# Schematic.net
KiCad netlist of a schematic drawn in Altium Designer
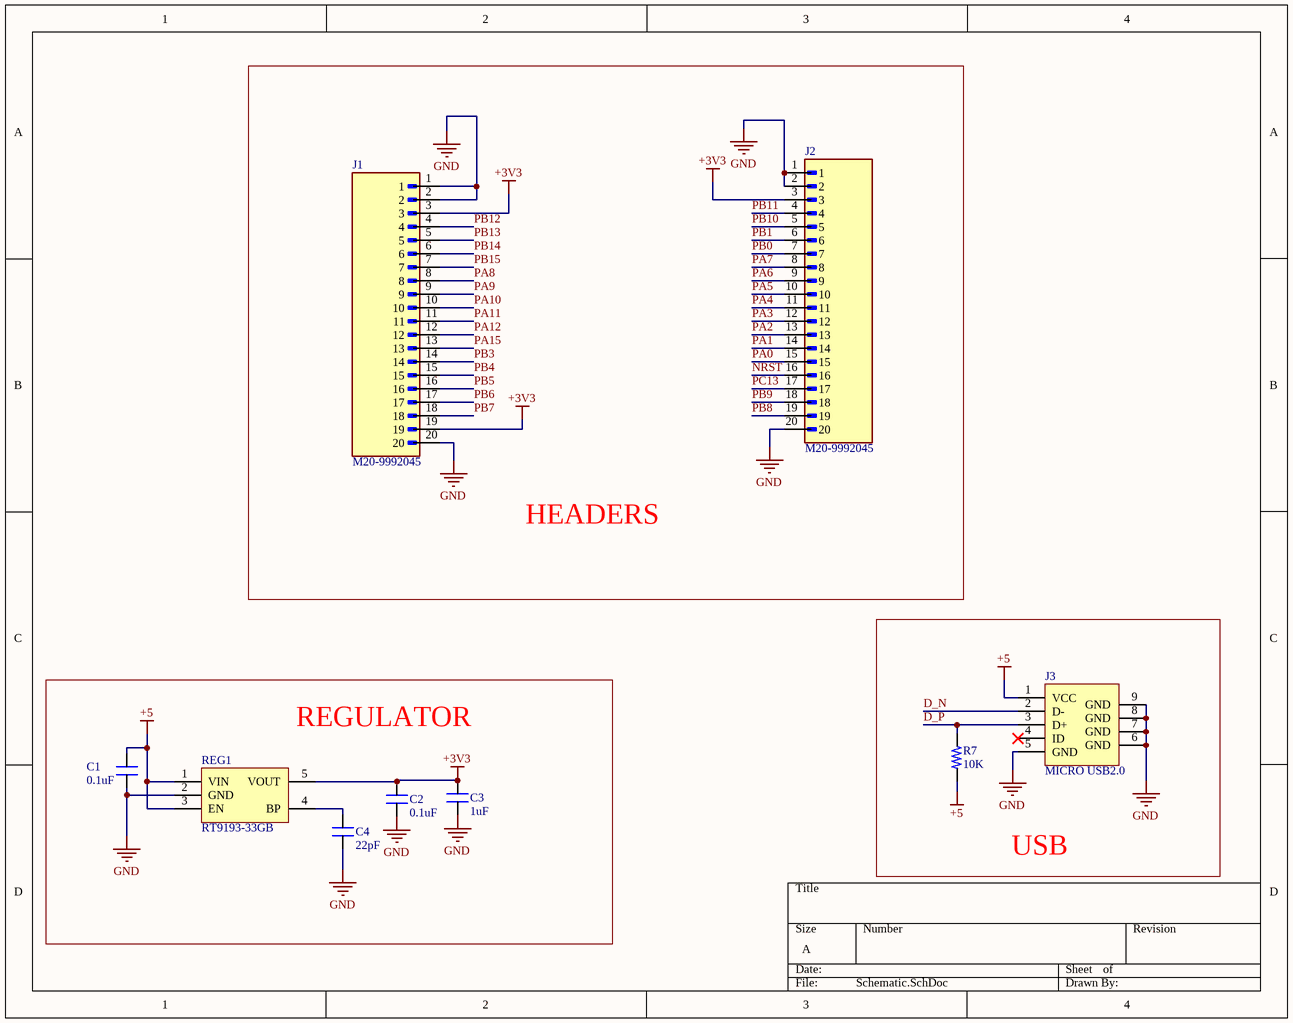
[diagram p0: Schematic.SchDoc]

(export (version "E")
  (design (tool "Eeschema 10.0.6"))
  (components
    (comp (ref "C1")
      (value "0.1uF")
      (footprint "CAP_0805")
      (description "0.1µF ±5% 50V Ceramic Capacitor X7R 0805 (2012 Metric)")
      (fields
        (field (name "MANUFACTURER") "KEMET")
        (field (name "MANUFACTURING PART NUMBER") "C0805C104J5RACTU")
      )
      (libsource (lib "STM_INT_LIB") (part "CAP_0.1uF-50V-5%-0805"))
    )
    (comp (ref "C2")
      (value "0.1uF")
      (footprint "CAP_0805")
      (description "0.1µF ±5% 50V Ceramic Capacitor X7R 0805 (2012 Metric)")
      (fields
        (field (name "MANUFACTURER") "KEMET")
        (field (name "MANUFACTURING PART NUMBER") "C0805C104J5RACTU")
      )
      (libsource (lib "STM_INT_LIB") (part "CAP_0.1uF-50V-5%-0805"))
    )
    (comp (ref "C3")
      (value "1uF")
      (footprint "CAP_0805")
      (description "1µF ±5% 50V Ceramic Capacitor X7R 0805 (2012 Metric)")
      (fields
        (field (name "MANUFACTURER") "Yageo")
        (field (name "MANUFACTURING PART NUMBER") "CC0805JKX7R9BB105")
      )
      (libsource (lib "STM_INT_LIB") (part "CAP_1uF-50V-5%-0805"))
    )
    (comp (ref "C4")
      (value "22pF")
      (footprint "CAP_0805")
      (description "22pF ±5% 50V Ceramic Capacitor C0G, NP0 0805 (2012 Metric)")
      (fields
        (field (name "MANUFACTURER") "KEMET")
        (field (name "MANUFACTURER PART NUMBER") "C0805C220J5GACTU")
      )
      (libsource (lib "STM_INT_LIB") (part "CAP_22pF-50V-5%-0805"))
    )
    (comp (ref "J1")
      (value "M20-9992045")
      (footprint "HARWIN_M20-9992045")
      (fields (field (name "MF") "Harwin"))
      (libsource (lib "20c") (part "M20-9992045"))
    )
    (comp (ref "J2")
      (value "M20-9992045")
      (footprint "HARWIN_M20-9992045")
      (fields (field (name "MF") "Harwin"))
      (libsource (lib "") (part "M20-9992045_1"))
    )
    (comp (ref "J3")
      (value "MICRO USB2.0")
      (footprint "CON_10118192-0001LF_SMD")
      (description "USB - micro B USB 2.0 Receptacle Connector 5 Position Surface Mount, Right Angle")
      (fields
        (field (name "MANUFACTURER") "Amphenol ICC (FCI)")
        (field (name "MANUFACTURING PART NUMBER") "10118192-0002LF")
      )
      (libsource (lib "STM_INT_LIB") (part "CON-USB_10118192-0002LF-SMD"))
    )
    (comp (ref "R7")
      (value "10K")
      (footprint "RES_0805")
      (description "10 kOhms ±1% 0.125W, 1/8W Chip Resistor 0805 (2012 Metric) Moisture Resistant Thick Film")
      (fields
        (field (name "MANUFACTURER") "Yageo")
        (field (name "MANUFACTURING PART NUMBER") "RC0805FR-0710KL")
      )
      (libsource (lib "STM_INT_LIB") (part "RES_10K-0.125W-1%-0805"))
    )
    (comp (ref "REG1")
      (value "RT9193-33GB")
      (footprint "SOT23-5")
      (description "Linear Voltage Regulator IC 1 Output 300mA SOT-23-5")
      (fields (field (name "MANUFACTURER") "Richtek USA Inc."))
      (libsource (lib "STM_INT_LIB") (part "REG_3.3V-5.5V-0.3A-SOT-23-5"))
    )
  )
  (nets
    (net (code "1") (name "+3V3") (class "Default")
      (node (ref "C2") (pin "2") (pinfunction "2_2") (pintype "passive"))
      (node (ref "C3") (pin "2") (pinfunction "2_2") (pintype "passive"))
      (node (ref "J1") (pin "19") (pinfunction "19_19") (pintype "passive"))
      (node (ref "J1") (pin "3") (pinfunction "3_3") (pintype "passive"))
      (node (ref "J2") (pin "3") (pinfunction "3_3") (pintype "passive"))
      (node (ref "REG1") (pin "5") (pinfunction "VOUT_5") (pintype "passive"))
    )
    (net (code "2") (name "+5") (class "Default")
      (node (ref "C1") (pin "2") (pinfunction "2_2") (pintype "passive"))
      (node (ref "J3") (pin "1") (pinfunction "VCC_1") (pintype "passive"))
      (node (ref "R7") (pin "1") (pinfunction "1_1") (pintype "passive"))
      (node (ref "REG1") (pin "1") (pinfunction "VIN_1") (pintype "passive"))
      (node (ref "REG1") (pin "3") (pinfunction "EN_3") (pintype "passive"))
    )
    (net (code "3") (name "/D_N") (class "Default")
      (node (ref "J3") (pin "2") (pinfunction "D-_2") (pintype "passive"))
    )
    (net (code "4") (name "/D_P") (class "Default")
      (node (ref "J3") (pin "3") (pinfunction "D+_3") (pintype "passive"))
      (node (ref "R7") (pin "2") (pinfunction "2_2") (pintype "passive"))
    )
    (net (code "5") (name "/NRST") (class "Default")
      (node (ref "J2") (pin "16") (pinfunction "16_16") (pintype "passive"))
    )
    (net (code "6") (name "/PA0") (class "Default")
      (node (ref "J2") (pin "15") (pinfunction "15_15") (pintype "passive"))
    )
    (net (code "7") (name "/PA1") (class "Default")
      (node (ref "J2") (pin "14") (pinfunction "14_14") (pintype "passive"))
    )
    (net (code "8") (name "/PA2") (class "Default")
      (node (ref "J2") (pin "13") (pinfunction "13_13") (pintype "passive"))
    )
    (net (code "9") (name "/PA3") (class "Default")
      (node (ref "J2") (pin "12") (pinfunction "12_12") (pintype "passive"))
    )
    (net (code "10") (name "/PA4") (class "Default")
      (node (ref "J2") (pin "11") (pinfunction "11_11") (pintype "passive"))
    )
    (net (code "11") (name "/PA5") (class "Default")
      (node (ref "J2") (pin "10") (pinfunction "10_10") (pintype "passive"))
    )
    (net (code "12") (name "/PA6") (class "Default")
      (node (ref "J2") (pin "9") (pinfunction "9_9") (pintype "passive"))
    )
    (net (code "13") (name "/PA7") (class "Default")
      (node (ref "J2") (pin "8") (pinfunction "8_8") (pintype "passive"))
    )
    (net (code "14") (name "/PA8") (class "Default")
      (node (ref "J1") (pin "8") (pinfunction "8_8") (pintype "passive"))
    )
    (net (code "15") (name "/PA9") (class "Default")
      (node (ref "J1") (pin "9") (pinfunction "9_9") (pintype "passive"))
    )
    (net (code "16") (name "/PA10") (class "Default")
      (node (ref "J1") (pin "10") (pinfunction "10_10") (pintype "passive"))
    )
    (net (code "17") (name "/PA11") (class "Default")
      (node (ref "J1") (pin "11") (pinfunction "11_11") (pintype "passive"))
    )
    (net (code "18") (name "/PA12") (class "Default")
      (node (ref "J1") (pin "12") (pinfunction "12_12") (pintype "passive"))
    )
    (net (code "19") (name "/PA15") (class "Default")
      (node (ref "J1") (pin "13") (pinfunction "13_13") (pintype "passive"))
    )
    (net (code "20") (name "/PB0") (class "Default")
      (node (ref "J2") (pin "7") (pinfunction "7_7") (pintype "passive"))
    )
    (net (code "21") (name "/PB1") (class "Default")
      (node (ref "J2") (pin "6") (pinfunction "6_6") (pintype "passive"))
    )
    (net (code "22") (name "/PB3") (class "Default")
      (node (ref "J1") (pin "14") (pinfunction "14_14") (pintype "passive"))
    )
    (net (code "23") (name "/PB4") (class "Default")
      (node (ref "J1") (pin "15") (pinfunction "15_15") (pintype "passive"))
    )
    (net (code "24") (name "/PB5") (class "Default")
      (node (ref "J1") (pin "16") (pinfunction "16_16") (pintype "passive"))
    )
    (net (code "25") (name "/PB6") (class "Default")
      (node (ref "J1") (pin "17") (pinfunction "17_17") (pintype "passive"))
    )
    (net (code "26") (name "/PB7") (class "Default")
      (node (ref "J1") (pin "18") (pinfunction "18_18") (pintype "passive"))
    )
    (net (code "27") (name "/PB8") (class "Default")
      (node (ref "J2") (pin "19") (pinfunction "19_19") (pintype "passive"))
    )
    (net (code "28") (name "/PB9") (class "Default")
      (node (ref "J2") (pin "18") (pinfunction "18_18") (pintype "passive"))
    )
    (net (code "29") (name "/PB10") (class "Default")
      (node (ref "J2") (pin "5") (pinfunction "5_5") (pintype "passive"))
    )
    (net (code "30") (name "/PB11") (class "Default")
      (node (ref "J2") (pin "4") (pinfunction "4_4") (pintype "passive"))
    )
    (net (code "31") (name "/PB12") (class "Default")
      (node (ref "J1") (pin "4") (pinfunction "4_4") (pintype "passive"))
    )
    (net (code "32") (name "/PB13") (class "Default")
      (node (ref "J1") (pin "5") (pinfunction "5_5") (pintype "passive"))
    )
    (net (code "33") (name "/PB14") (class "Default")
      (node (ref "J1") (pin "6") (pinfunction "6_6") (pintype "passive"))
    )
    (net (code "34") (name "/PB15") (class "Default")
      (node (ref "J1") (pin "7") (pinfunction "7_7") (pintype "passive"))
    )
    (net (code "35") (name "/PC13") (class "Default")
      (node (ref "J2") (pin "17") (pinfunction "17_17") (pintype "passive"))
    )
    (net (code "36") (name "GND") (class "Default")
      (node (ref "C1") (pin "1") (pinfunction "1_1") (pintype "passive"))
      (node (ref "C2") (pin "1") (pinfunction "1_1") (pintype "passive"))
      (node (ref "C3") (pin "1") (pinfunction "1_1") (pintype "passive"))
      (node (ref "C4") (pin "1") (pinfunction "1_1") (pintype "passive"))
      (node (ref "J1") (pin "1") (pinfunction "1_1") (pintype "passive"))
      (node (ref "J1") (pin "2") (pinfunction "2_2") (pintype "passive"))
      (node (ref "J1") (pin "20") (pinfunction "20_20") (pintype "passive"))
      (node (ref "J2") (pin "1") (pinfunction "1_1") (pintype "passive"))
      (node (ref "J2") (pin "2") (pinfunction "2_2") (pintype "passive"))
      (node (ref "J2") (pin "20") (pinfunction "20_20") (pintype "passive"))
      (node (ref "J3") (pin "5") (pinfunction "GND_5") (pintype "passive"))
      (node (ref "J3") (pin "6") (pinfunction "GND_6") (pintype "passive"))
      (node (ref "J3") (pin "7") (pinfunction "GND_7") (pintype "passive"))
      (node (ref "J3") (pin "8") (pinfunction "GND_8") (pintype "passive"))
      (node (ref "J3") (pin "9") (pinfunction "GND_9") (pintype "passive"))
      (node (ref "REG1") (pin "2") (pinfunction "GND_2") (pintype "passive"))
    )
    (net (code "37") (name "Net-(REG1-BP)") (class "Default")
      (node (ref "C4") (pin "2") (pinfunction "2_2") (pintype "passive"))
      (node (ref "REG1") (pin "4") (pinfunction "BP_4") (pintype "passive"))
    )
    (net (code "38") (name "unconnected-(J3-ID-Pad4)") (class "Default")
      (node (ref "J3") (pin "4") (pinfunction "ID_4") (pintype "passive+no_connect"))
    )
  )
)
